# driver.net
KiCad netlist of a schematic drawn in Altium Designer
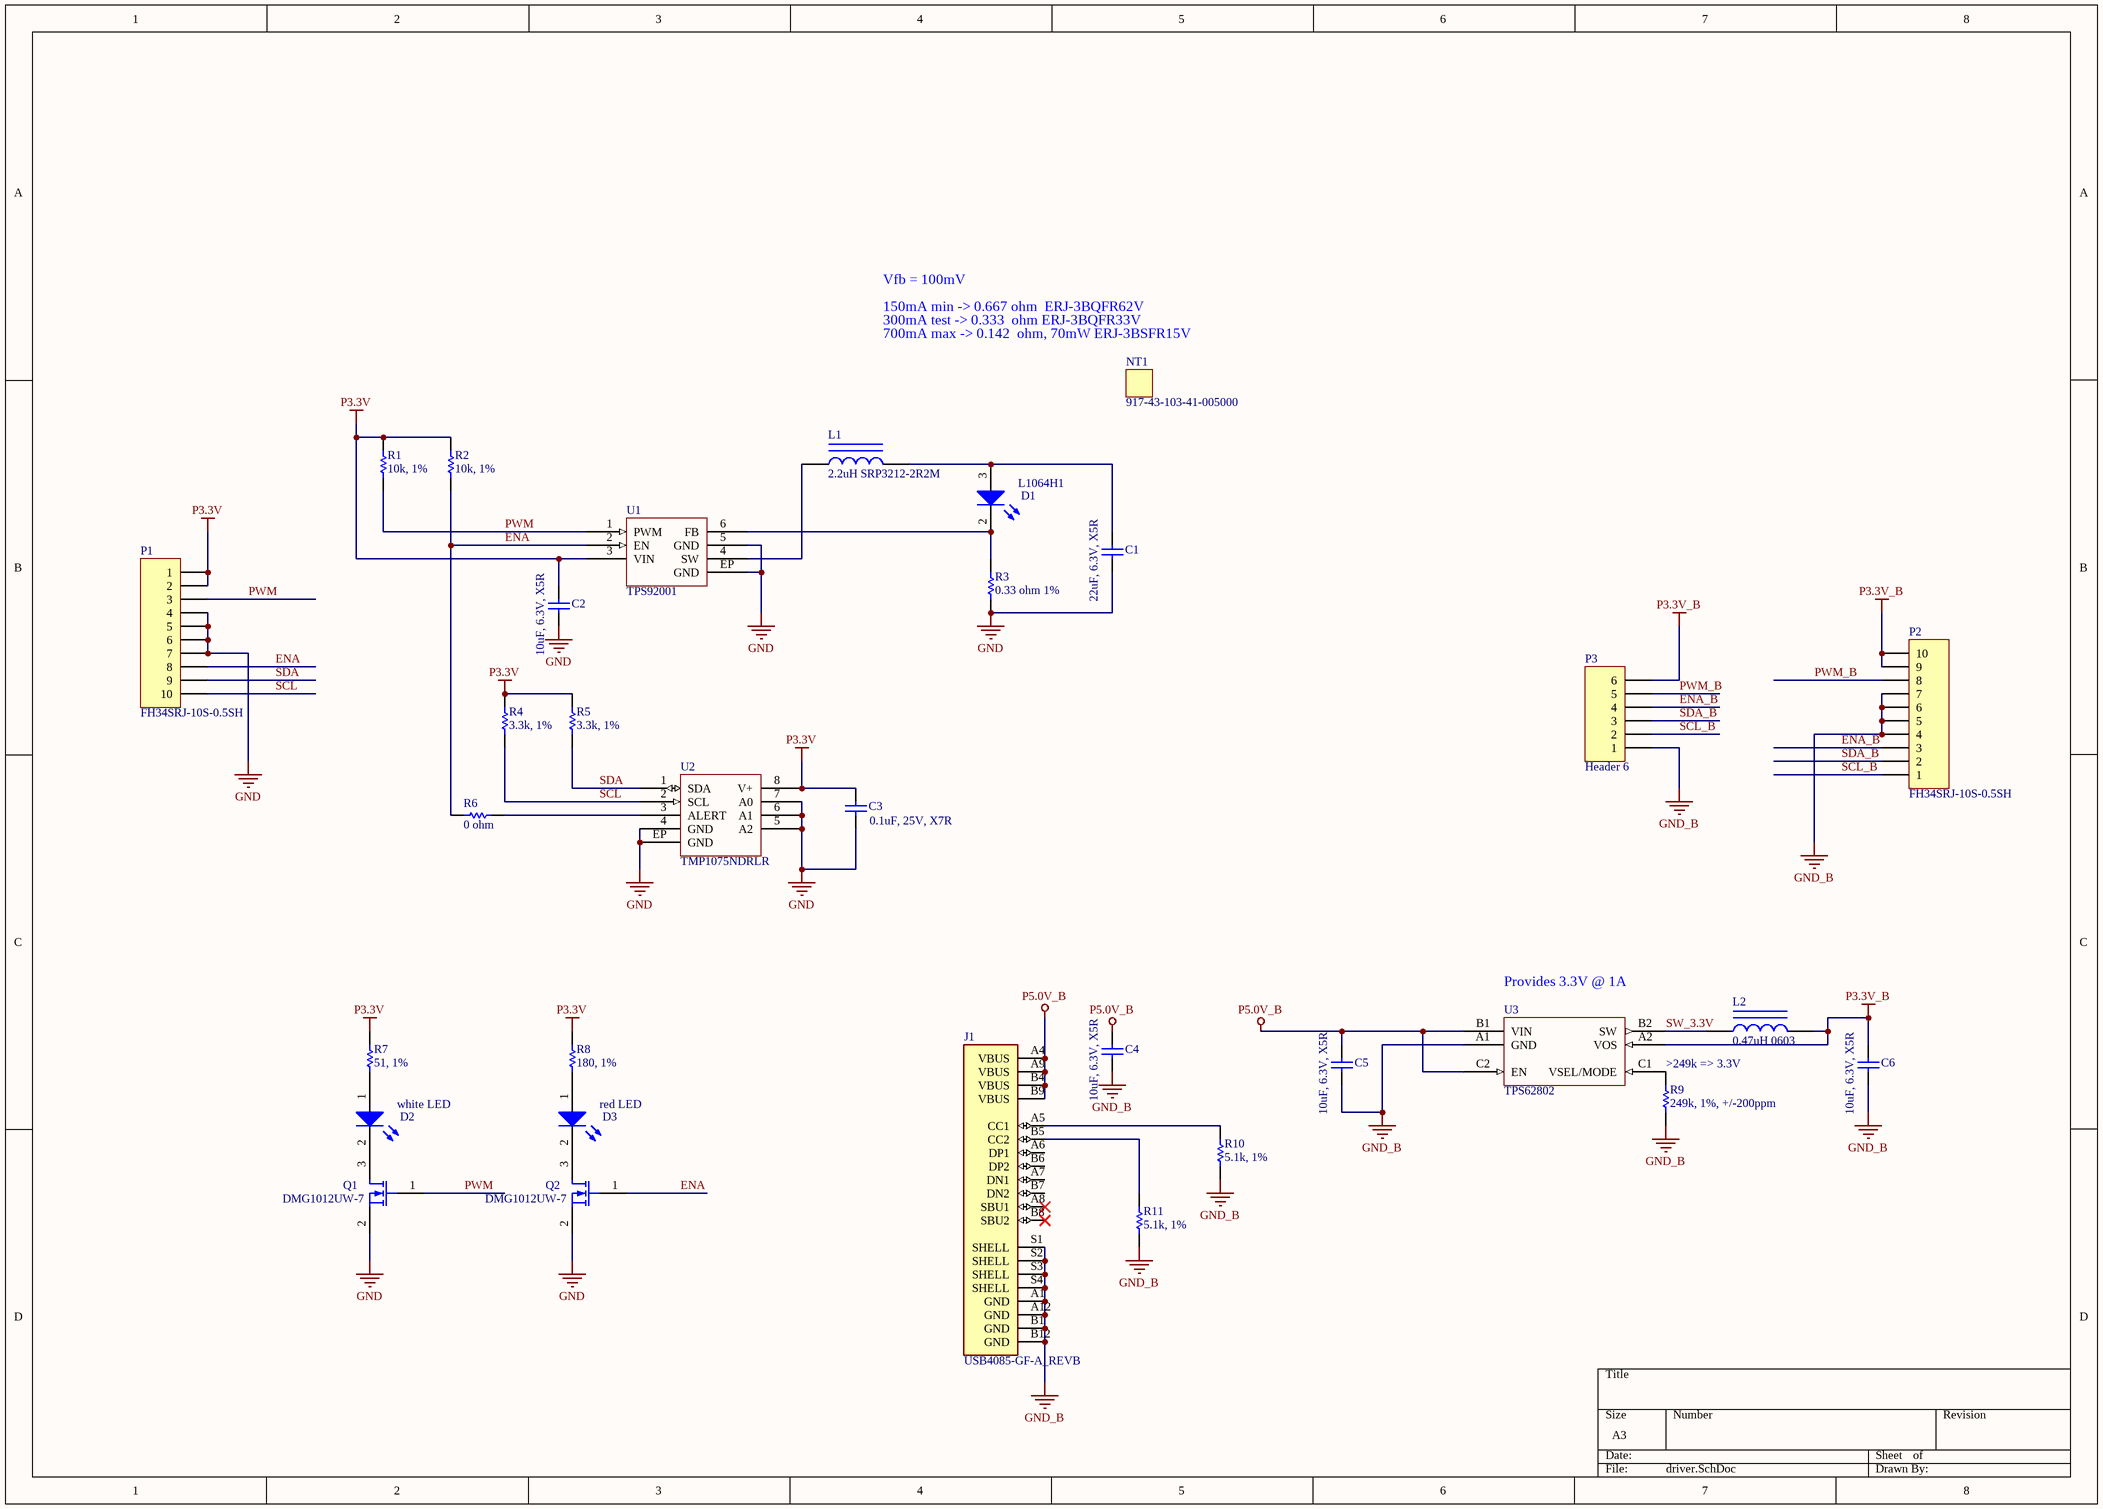
[diagram p0: driver.SchDoc]

(export (version "E")
  (design (tool "Eeschema 10.0.6"))
  (components
    (comp (ref "C1")
      (value "22uF, 6.3V, X5R")
      (footprint "B_CAP0603")
      (description "Capacitor (Semiconductor SIM Model)")
      (fields (field (name "MPN") "CL10A226KQ8NRNE"))
      (libsource (lib "Miscellaneous Devices") (part "Cap Semi"))
    )
    (comp (ref "C2")
      (value "10uF, 6.3V, X5R")
      (footprint "B_CAP0603")
      (description "Capacitor (Semiconductor SIM Model)")
      (fields (field (name "MPN") "CL10A106MQ8NNNC"))
      (libsource (lib "Miscellaneous Devices") (part "Cap Semi"))
    )
    (comp (ref "C3")
      (value "0.1uF, 25V, X7R")
      (footprint "B_CAP0402")
      (description "Capacitor (Semiconductor SIM Model)")
      (fields (field (name "MPN") "CL05A104KA5NNNC"))
      (libsource (lib "Miscellaneous Devices") (part "Cap Semi"))
    )
    (comp (ref "C4")
      (value "10uF, 6.3V, X5R")
      (footprint "B_CAP0603")
      (description "Capacitor (Semiconductor SIM Model)")
      (fields (field (name "MPN") "CL10A106MQ8NNNC"))
      (libsource (lib "Miscellaneous Devices") (part "Cap Semi"))
    )
    (comp (ref "C5")
      (value "10uF, 6.3V, X5R")
      (footprint "B_CAP0603")
      (description "Capacitor (Semiconductor SIM Model)")
      (fields (field (name "MPN") "CL10A106MQ8NNNC"))
      (libsource (lib "Miscellaneous Devices") (part "Cap Semi"))
    )
    (comp (ref "C6")
      (value "10uF, 6.3V, X5R")
      (footprint "B_CAP0603")
      (description "Capacitor (Semiconductor SIM Model)")
      (fields (field (name "MPN") "CL10A106MQ8NNNC"))
      (libsource (lib "Miscellaneous Devices") (part "Cap Semi"))
    )
    (comp (ref "D1")
      (value "L1064H1")
      (footprint "TO-CAN-MICROJACK")
      (description "Typical RED, GREEN, YELLOW, AMBER GaAs LED")
      (libsource (lib "") (part "LED2_1"))
    )
    (comp (ref "D2")
      (value "white LED")
      (footprint "B_LED0805")
      (description "Typical RED, GREEN, YELLOW, AMBER GaAs LED")
      (fields (field (name "MPN") "EAST2012WA1"))
      (libsource (lib "Miscellaneous Devices") (part "LED2"))
    )
    (comp (ref "D3")
      (value "red LED")
      (footprint "B_LED0805")
      (description "Typical RED, GREEN, YELLOW, AMBER GaAs LED")
      (fields (field (name "MPN") "ANY"))
      (libsource (lib "Miscellaneous Devices") (part "LED2"))
    )
    (comp (ref "J1")
      (value "USB4085-GF-A_REVB")
      (footprint "GCT_USB4085-GF-A_REVB")
      (fields (field (name "MF") "Global Connector Technology") (field (name "MP") "USB4085-GF-A"))
      (libsource (lib "USB4085-GF-A_REVB") (part "USB4085-GF-A_REVB"))
    )
    (comp (ref "L1")
      (value "2.2uH SRP3212-2R2M")
      (footprint "B_IND1210_BOURNES")
      (description "Magnetic-Core Inductor")
      (fields (field (name "MPN") "SRP3212-2R2M"))
      (libsource (lib "Miscellaneous Devices") (part "Inductor Iron"))
    )
    (comp (ref "L2")
      (value "0.47uH 0603")
      (footprint "B_IND0603")
      (description "Magnetic-Core Inductor")
      (fields (field (name "MPN") "TFM160808ALC-R47MTAA"))
      (libsource (lib "Miscellaneous Devices") (part "Inductor Iron"))
    )
    (comp (ref "NT1")
      (value "917-43-103-41-005000")
      (description "Placeholder for non-board BOM items")
      (libsource (lib "commonsch") (part "NOTE"))
    )
    (comp (ref "P1")
      (value "FH34SRJ-10S-0.5SH")
      (footprint "HRS_FH34SRJ-10S-0.5SH(50)")
      (description "Header, 10-Pin")
      (fields (field (name "PUBLISHER") "Altium Limited"))
      (libsource (lib "") (part "Header 10_1"))
    )
    (comp (ref "P2")
      (value "FH34SRJ-10S-0.5SH")
      (footprint "HRS_FH34SRJ-10S-0.5SH(50)")
      (description "Header, 10-Pin")
      (fields (field (name "PUBLISHER") "Altium Limited"))
      (libsource (lib "Miscellaneous Connectors") (part "Header 10"))
    )
    (comp (ref "P3")
      (value "Header 6")
      (footprint "HDR1X6")
      (description "Header, 6-Pin")
      (fields (field (name "PUBLISHER") "Altium Limited"))
      (libsource (lib "Miscellaneous Connectors") (part "Header 6"))
    )
    (comp (ref "Q1")
      (value "DMG1012UW-7")
      (footprint "SOT323-3AN")
      (description "N-Channel MOSFET")
      (fields (field (name "PUBLISHER") "Altium Limited"))
      (libsource (lib "Miscellaneous Devices") (part "MOSFET-N"))
    )
    (comp (ref "Q2")
      (value "DMG1012UW-7")
      (footprint "SOT323-3AN")
      (description "N-Channel MOSFET")
      (fields (field (name "PUBLISHER") "Altium Limited"))
      (libsource (lib "Miscellaneous Devices") (part "MOSFET-N"))
    )
    (comp (ref "R1")
      (value "10k, 1%")
      (footprint "B_RES0402")
      (description "Resistor")
      (fields (field (name "MPN") "ANY"))
      (libsource (lib "Miscellaneous Devices") (part "Res1"))
    )
    (comp (ref "R2")
      (value "10k, 1%")
      (footprint "B_RES0402")
      (description "Resistor")
      (fields (field (name "MPN") "ANY"))
      (libsource (lib "Miscellaneous Devices") (part "Res1"))
    )
    (comp (ref "R3")
      (value "0.33 ohm 1%")
      (footprint "B_RES0603")
      (description "Resistor")
      (fields (field (name "MPN") "ERJ-3BQFR33V"))
      (libsource (lib "Miscellaneous Devices") (part "Res1"))
    )
    (comp (ref "R4")
      (value "3.3k, 1%")
      (footprint "B_RES0402")
      (description "Resistor")
      (fields (field (name "MPN") "ANY"))
      (libsource (lib "Miscellaneous Devices") (part "Res1"))
    )
    (comp (ref "R5")
      (value "3.3k, 1%")
      (footprint "B_RES0402")
      (description "Resistor")
      (fields (field (name "MPN") "ANY"))
      (libsource (lib "Miscellaneous Devices") (part "Res1"))
    )
    (comp (ref "R6")
      (value "0 ohm")
      (footprint "B_RES0402")
      (description "Resistor")
      (fields (field (name "MPN") "ANY"))
      (libsource (lib "Miscellaneous Devices") (part "Res1"))
    )
    (comp (ref "R7")
      (value "51, 1%")
      (footprint "B_RES0603")
      (description "Resistor")
      (fields (field (name "MPN") "ANY"))
      (libsource (lib "Miscellaneous Devices") (part "Res1"))
    )
    (comp (ref "R8")
      (value "180, 1%")
      (footprint "B_RES0603")
      (description "Resistor")
      (fields (field (name "MPN") "ANY"))
      (libsource (lib "Miscellaneous Devices") (part "Res1"))
    )
    (comp (ref "R9")
      (value "249k, 1%, +/-200ppm")
      (footprint "B_RES0402")
      (description "Resistor")
      (fields (field (name "MPN") "RC0402FR-07249KL"))
      (libsource (lib "Miscellaneous Devices") (part "Res1"))
    )
    (comp (ref "R10")
      (value "5.1k, 1%")
      (footprint "B_RES0603")
      (description "Resistor")
      (fields (field (name "MPN") "RC0603FR-075K1L"))
      (libsource (lib "Miscellaneous Devices") (part "Res1"))
    )
    (comp (ref "R11")
      (value "5.1k, 1%")
      (footprint "B_RES0603")
      (description "Resistor")
      (fields (field (name "MPN") "RC0603FR-075K1L"))
      (libsource (lib "Miscellaneous Devices") (part "Res1"))
    )
    (comp (ref "U1")
      (value "TPS92001")
      (footprint "TI-WSON65P200X80_HS-7N")
      (description "1.5A high efficiency synchronous buck LED driver")
      (libsource (lib "commonsch-new") (part "TPS92201"))
    )
    (comp (ref "U2")
      (value "TMP1075NDRLR")
      (footprint "TI-SON50P200X80_HS-9N")
      (description "Temperature sensor, I2C")
      (libsource (lib "commonsch-new") (part "TMP1075N"))
    )
    (comp (ref "U3")
      (value "TPS62802")
      (footprint "BGA6C35P2X3_70X105X40_NSMD")
      (description "Buck regulator, 4MHz, 0.6A, 1.8V-3.3V, low Iq")
      (fields (field (name "MPN") "TPS62802YKAR"))
      (libsource (lib "altium-import") (part "root_0_TPS62802_"))
    )
  )
  (nets
    (net (code "1") (name "/ENA") (class "Default")
      (node (ref "P1") (pin "8") (pinfunction "8_8") (pintype "passive"))
      (node (ref "Q2") (pin "1") (pinfunction "G_1") (pintype "passive"))
      (node (ref "R2") (pin "1") (pinfunction "1_1") (pintype "passive"))
      (node (ref "R6") (pin "1") (pinfunction "1_1") (pintype "passive"))
      (node (ref "U1") (pin "2") (pinfunction "EN_2") (pintype "input"))
    )
    (net (code "2") (name "/ENA_B") (class "Default")
      (node (ref "P2") (pin "3") (pinfunction "3_3") (pintype "passive"))
      (node (ref "P3") (pin "4") (pinfunction "4_4") (pintype "passive"))
    )
    (net (code "3") (name "/PWM") (class "Default")
      (node (ref "P1") (pin "3") (pinfunction "3_3") (pintype "passive"))
      (node (ref "Q1") (pin "1") (pinfunction "G_1") (pintype "passive"))
      (node (ref "R1") (pin "1") (pinfunction "1_1") (pintype "passive"))
      (node (ref "U1") (pin "1") (pinfunction "PWM_1") (pintype "input"))
    )
    (net (code "4") (name "/PWM_B") (class "Default")
      (node (ref "P2") (pin "8") (pinfunction "8_8") (pintype "passive"))
      (node (ref "P3") (pin "5") (pinfunction "5_5") (pintype "passive"))
    )
    (net (code "5") (name "/SCL") (class "Default")
      (node (ref "P1") (pin "10") (pinfunction "10_10") (pintype "passive"))
      (node (ref "R4") (pin "1") (pinfunction "1_1") (pintype "passive"))
      (node (ref "U2") (pin "2") (pinfunction "SCL_2") (pintype "input"))
    )
    (net (code "6") (name "/SCL_B") (class "Default")
      (node (ref "P2") (pin "1") (pinfunction "1_1") (pintype "passive"))
      (node (ref "P3") (pin "2") (pinfunction "2_2") (pintype "passive"))
    )
    (net (code "7") (name "/SDA") (class "Default")
      (node (ref "P1") (pin "9") (pinfunction "9_9") (pintype "passive"))
      (node (ref "R5") (pin "1") (pinfunction "1_1") (pintype "passive"))
      (node (ref "U2") (pin "1") (pinfunction "SDA_1") (pintype "bidirectional"))
    )
    (net (code "8") (name "/SDA_B") (class "Default")
      (node (ref "P2") (pin "2") (pinfunction "2_2") (pintype "passive"))
      (node (ref "P3") (pin "3") (pinfunction "3_3") (pintype "passive"))
    )
    (net (code "9") (name "/SW_3.3V") (class "Default")
      (node (ref "L2") (pin "1") (pinfunction "1_1") (pintype "passive"))
      (node (ref "U3") (pin "B2") (pinfunction "SW_B2") (pintype "output"))
    )
    (net (code "10") (name "GND") (class "Default")
      (node (ref "C1") (pin "2") (pinfunction "2_2") (pintype "passive"))
      (node (ref "C2") (pin "2") (pinfunction "2_2") (pintype "passive"))
      (node (ref "C3") (pin "2") (pinfunction "2_2") (pintype "passive"))
      (node (ref "P1") (pin "4") (pinfunction "4_4") (pintype "passive"))
      (node (ref "P1") (pin "5") (pinfunction "5_5") (pintype "passive"))
      (node (ref "P1") (pin "6") (pinfunction "6_6") (pintype "passive"))
      (node (ref "P1") (pin "7") (pinfunction "7_7") (pintype "passive"))
      (node (ref "Q1") (pin "2") (pinfunction "S_2") (pintype "passive"))
      (node (ref "Q2") (pin "2") (pinfunction "S_2") (pintype "passive"))
      (node (ref "R3") (pin "2") (pinfunction "2_2") (pintype "passive"))
      (node (ref "U1") (pin "5") (pinfunction "GND_5") (pintype "power_in"))
      (node (ref "U1") (pin "EP") (pinfunction "GND_EP") (pintype "passive"))
      (node (ref "U2") (pin "4") (pinfunction "GND_4") (pintype "power_in"))
      (node (ref "U2") (pin "5") (pinfunction "A2_5") (pintype "passive"))
      (node (ref "U2") (pin "6") (pinfunction "A1_6") (pintype "passive"))
      (node (ref "U2") (pin "7") (pinfunction "A0_7") (pintype "passive"))
      (node (ref "U2") (pin "EP") (pinfunction "GND_EP") (pintype "power_in"))
    )
    (net (code "11") (name "GND_B") (class "Default")
      (node (ref "C4") (pin "2") (pinfunction "2_2") (pintype "passive"))
      (node (ref "C5") (pin "2") (pinfunction "2_2") (pintype "passive"))
      (node (ref "C6") (pin "2") (pinfunction "2_2") (pintype "passive"))
      (node (ref "J1") (pin "A1") (pinfunction "GND_A1") (pintype "power_in"))
      (node (ref "J1") (pin "A12") (pinfunction "GND_A12") (pintype "power_in"))
      (node (ref "J1") (pin "B1") (pinfunction "GND_B1") (pintype "power_in"))
      (node (ref "J1") (pin "B12") (pinfunction "GND_B12") (pintype "power_in"))
      (node (ref "J1") (pin "S1") (pinfunction "SHELL_S1") (pintype "passive"))
      (node (ref "J1") (pin "S2") (pinfunction "SHELL_S2") (pintype "passive"))
      (node (ref "J1") (pin "S3") (pinfunction "SHELL_S3") (pintype "passive"))
      (node (ref "J1") (pin "S4") (pinfunction "SHELL_S4") (pintype "passive"))
      (node (ref "P2") (pin "4") (pinfunction "4_4") (pintype "passive"))
      (node (ref "P2") (pin "5") (pinfunction "5_5") (pintype "passive"))
      (node (ref "P2") (pin "6") (pinfunction "6_6") (pintype "passive"))
      (node (ref "P2") (pin "7") (pinfunction "7_7") (pintype "passive"))
      (node (ref "P3") (pin "1") (pinfunction "1_1") (pintype "passive"))
      (node (ref "R10") (pin "1") (pinfunction "1_1") (pintype "passive"))
      (node (ref "R11") (pin "1") (pinfunction "1_1") (pintype "passive"))
      (node (ref "R9") (pin "2") (pinfunction "2_2") (pintype "passive"))
      (node (ref "U3") (pin "A1") (pinfunction "GND_A1") (pintype "power_in"))
    )
    (net (code "12") (name "Net-(D1-A)") (class "Default")
      (node (ref "C1") (pin "1") (pinfunction "1_1") (pintype "passive"))
      (node (ref "D1") (pin "3") (pinfunction "A_3") (pintype "passive"))
      (node (ref "L1") (pin "2") (pinfunction "2_2") (pintype "passive"))
    )
    (net (code "13") (name "Net-(D1-K)") (class "Default")
      (node (ref "D1") (pin "2") (pinfunction "K_2") (pintype "passive"))
      (node (ref "R3") (pin "1") (pinfunction "1_1") (pintype "passive"))
      (node (ref "U1") (pin "6") (pinfunction "FB_6") (pintype "passive"))
    )
    (net (code "14") (name "Net-(D2-A)") (class "Default")
      (node (ref "D2") (pin "1") (pinfunction "A_1") (pintype "passive"))
      (node (ref "R7") (pin "1") (pinfunction "1_1") (pintype "passive"))
    )
    (net (code "15") (name "Net-(D2-K)") (class "Default")
      (node (ref "D2") (pin "2") (pinfunction "K_2") (pintype "passive"))
      (node (ref "Q1") (pin "3") (pinfunction "D_3") (pintype "passive"))
    )
    (net (code "16") (name "Net-(D3-A)") (class "Default")
      (node (ref "D3") (pin "1") (pinfunction "A_1") (pintype "passive"))
      (node (ref "R8") (pin "1") (pinfunction "1_1") (pintype "passive"))
    )
    (net (code "17") (name "Net-(D3-K)") (class "Default")
      (node (ref "D3") (pin "2") (pinfunction "K_2") (pintype "passive"))
      (node (ref "Q2") (pin "3") (pinfunction "D_3") (pintype "passive"))
    )
    (net (code "18") (name "Net-(J1-CC1)") (class "Default")
      (node (ref "J1") (pin "A5") (pinfunction "CC1_A5") (pintype "bidirectional"))
      (node (ref "R10") (pin "2") (pinfunction "2_2") (pintype "passive"))
    )
    (net (code "19") (name "Net-(J1-CC2)") (class "Default")
      (node (ref "J1") (pin "B5") (pinfunction "CC2_B5") (pintype "bidirectional"))
      (node (ref "R11") (pin "2") (pinfunction "2_2") (pintype "passive"))
    )
    (net (code "20") (name "Net-(U1-SW)") (class "Default")
      (node (ref "L1") (pin "1") (pinfunction "1_1") (pintype "passive"))
      (node (ref "U1") (pin "4") (pinfunction "SW_4") (pintype "passive"))
    )
    (net (code "21") (name "Net-(U2-ALERT)") (class "Default")
      (node (ref "R6") (pin "2") (pinfunction "2_2") (pintype "passive"))
      (node (ref "U2") (pin "3") (pinfunction "ALERT_3") (pintype "passive"))
    )
    (net (code "22") (name "Net-(U3-VSEL{slash}MODE)") (class "Default")
      (node (ref "R9") (pin "1") (pinfunction "1_1") (pintype "passive"))
      (node (ref "U3") (pin "C1") (pinfunction "VSEL/MODE_C1") (pintype "input"))
    )
    (net (code "23") (name "P3.3V") (class "Default")
      (node (ref "C2") (pin "1") (pinfunction "1_1") (pintype "passive"))
      (node (ref "C3") (pin "1") (pinfunction "1_1") (pintype "passive"))
      (node (ref "P1") (pin "1") (pinfunction "1_1") (pintype "passive"))
      (node (ref "P1") (pin "2") (pinfunction "2_2") (pintype "passive"))
      (node (ref "R1") (pin "2") (pinfunction "2_2") (pintype "passive"))
      (node (ref "R2") (pin "2") (pinfunction "2_2") (pintype "passive"))
      (node (ref "R4") (pin "2") (pinfunction "2_2") (pintype "passive"))
      (node (ref "R5") (pin "2") (pinfunction "2_2") (pintype "passive"))
      (node (ref "R7") (pin "2") (pinfunction "2_2") (pintype "passive"))
      (node (ref "R8") (pin "2") (pinfunction "2_2") (pintype "passive"))
      (node (ref "U1") (pin "3") (pinfunction "VIN_3") (pintype "power_in"))
      (node (ref "U2") (pin "8") (pinfunction "V+_8") (pintype "power_in"))
    )
    (net (code "24") (name "P3.3V_B") (class "Default")
      (node (ref "C6") (pin "1") (pinfunction "1_1") (pintype "passive"))
      (node (ref "L2") (pin "2") (pinfunction "2_2") (pintype "passive"))
      (node (ref "P2") (pin "10") (pinfunction "10_10") (pintype "passive"))
      (node (ref "P2") (pin "9") (pinfunction "9_9") (pintype "passive"))
      (node (ref "P3") (pin "6") (pinfunction "6_6") (pintype "passive"))
      (node (ref "U3") (pin "A2") (pinfunction "VOS_A2") (pintype "input"))
    )
    (net (code "25") (name "P5.0V_B") (class "Default")
      (node (ref "C4") (pin "1") (pinfunction "1_1") (pintype "passive"))
      (node (ref "C5") (pin "1") (pinfunction "1_1") (pintype "passive"))
      (node (ref "J1") (pin "A4") (pinfunction "VBUS_A4") (pintype "power_in"))
      (node (ref "J1") (pin "A9") (pinfunction "VBUS_A9") (pintype "power_in"))
      (node (ref "J1") (pin "B4") (pinfunction "VBUS_B4") (pintype "power_in"))
      (node (ref "J1") (pin "B9") (pinfunction "VBUS_B9") (pintype "power_in"))
      (node (ref "U3") (pin "B1") (pinfunction "VIN_B1") (pintype "power_in"))
      (node (ref "U3") (pin "C2") (pinfunction "EN_C2") (pintype "input"))
    )
    (net (code "26") (name "unconnected-(J1-DN1-PadA7)") (class "Default")
      (node (ref "J1") (pin "A7") (pinfunction "DN1_A7") (pintype "bidirectional"))
    )
    (net (code "27") (name "unconnected-(J1-DN2-PadB7)") (class "Default")
      (node (ref "J1") (pin "B7") (pinfunction "DN2_B7") (pintype "bidirectional"))
    )
    (net (code "28") (name "unconnected-(J1-DP1-PadA6)") (class "Default")
      (node (ref "J1") (pin "A6") (pinfunction "DP1_A6") (pintype "bidirectional"))
    )
    (net (code "29") (name "unconnected-(J1-DP2-PadB6)") (class "Default")
      (node (ref "J1") (pin "B6") (pinfunction "DP2_B6") (pintype "bidirectional"))
    )
    (net (code "30") (name "unconnected-(J1-SBU1-PadA8)") (class "Default")
      (node (ref "J1") (pin "A8") (pinfunction "SBU1_A8") (pintype "bidirectional+no_connect"))
    )
    (net (code "31") (name "unconnected-(J1-SBU2-PadB8)") (class "Default")
      (node (ref "J1") (pin "B8") (pinfunction "SBU2_B8") (pintype "bidirectional+no_connect"))
    )
  )
)
